# Caution_Panel_control.net
KiCad netlist of a schematic drawn in EAGLE
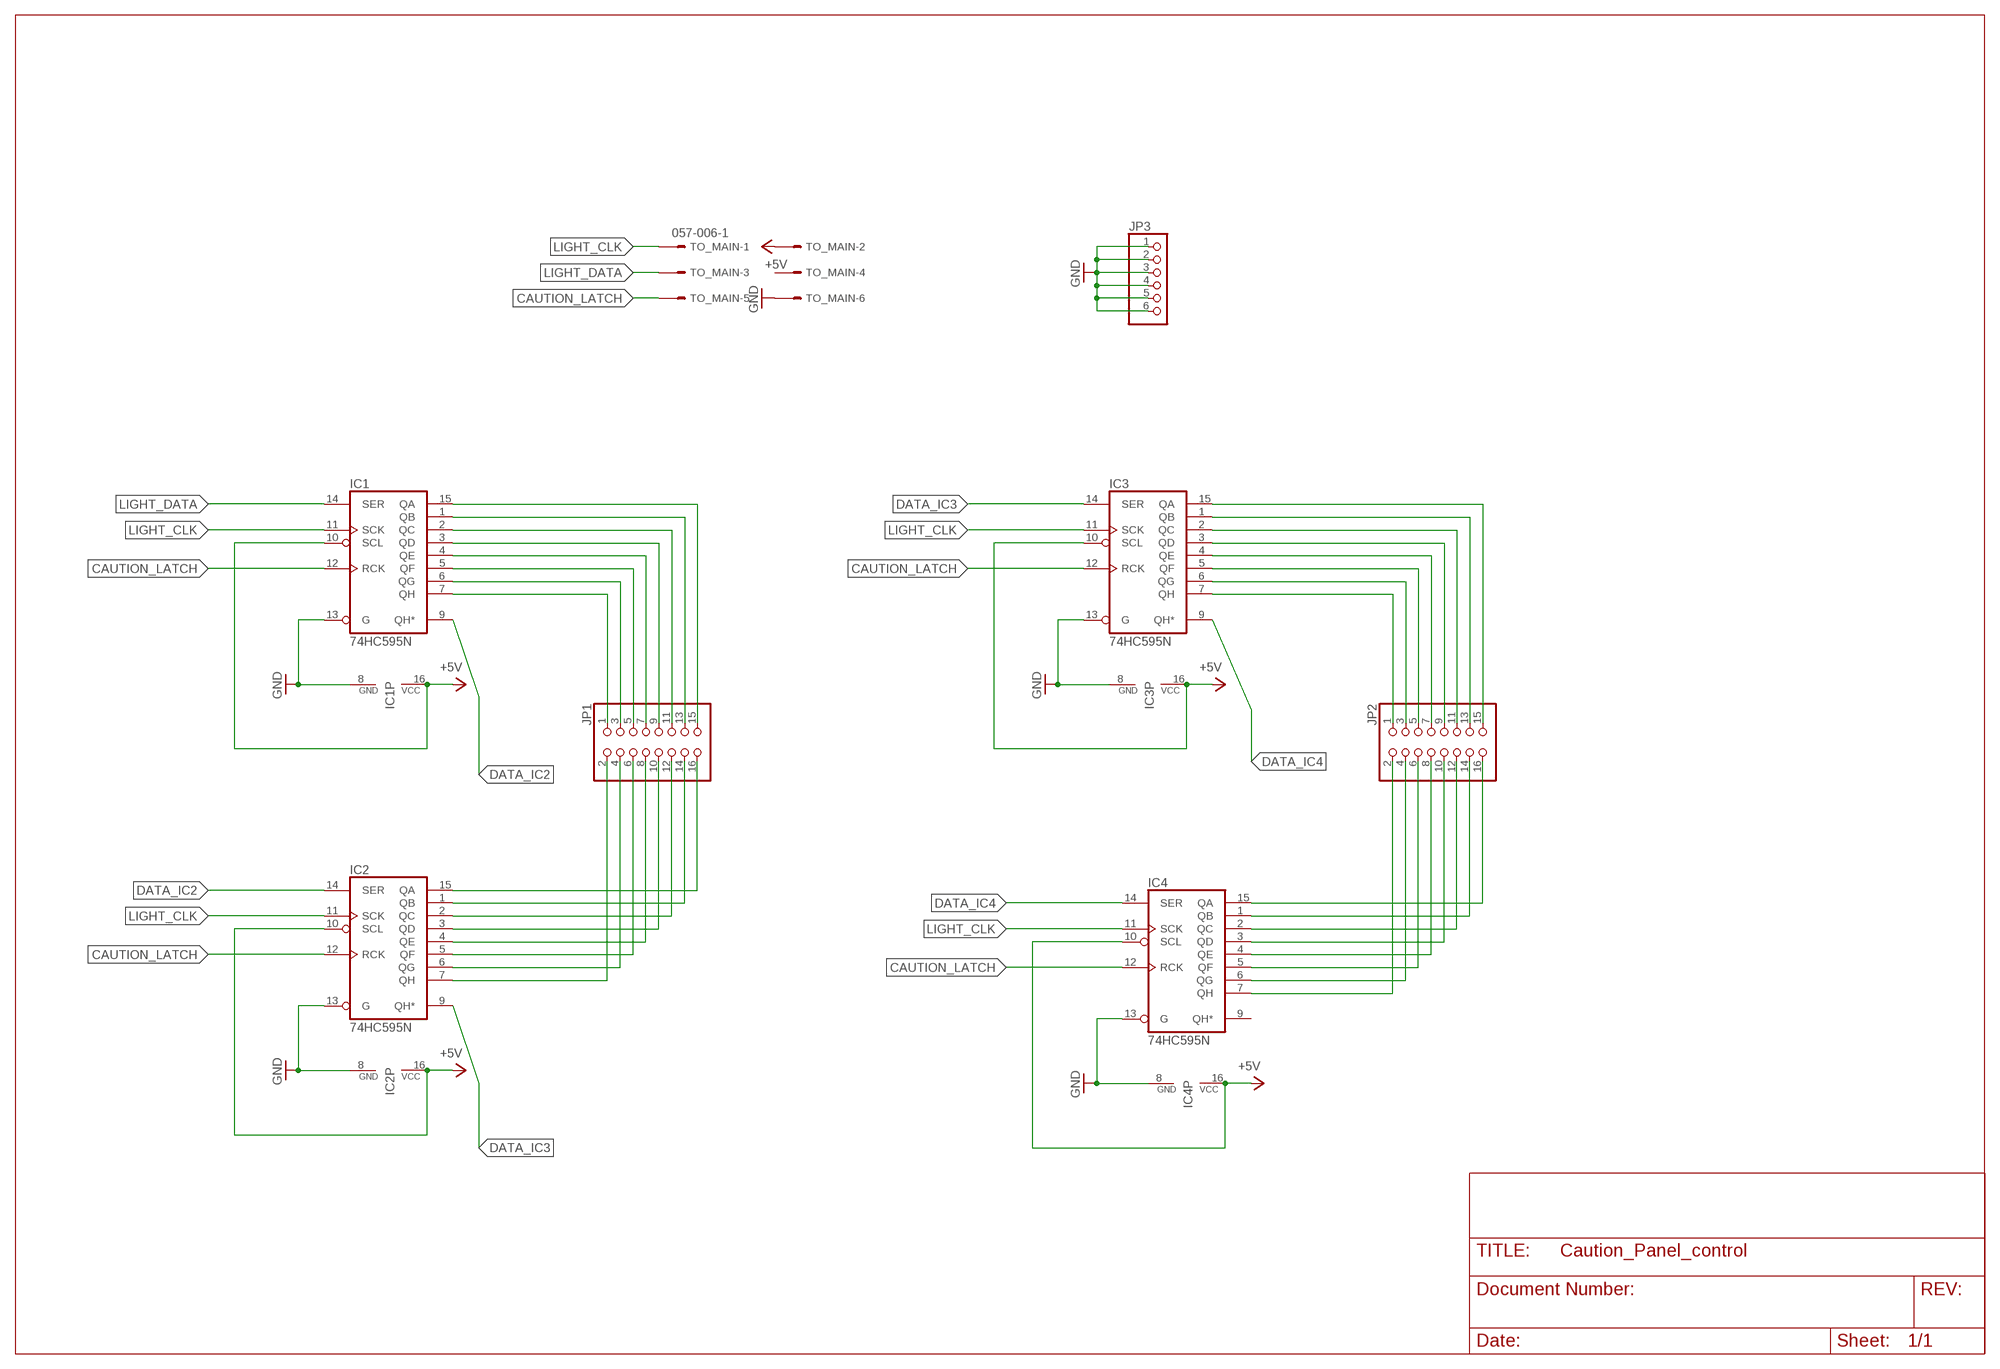
[diagram p0: schematic, sheet 1]

(export (version "E")
  (design (tool "Eeschema 10.0.6"))
  (components
    (comp (ref "IC1")
      (value "74HC595N")
      (footprint "eagle-import:DIL16")
      (libsource (lib "eagle-import") (part "74595NHC"))
    )
    (comp (ref "IC2")
      (value "74HC595N")
      (footprint "eagle-import:DIL16")
      (libsource (lib "eagle-import") (part "74595NHC"))
    )
    (comp (ref "IC3")
      (value "74HC595N")
      (footprint "eagle-import:DIL16")
      (libsource (lib "eagle-import") (part "74595NHC"))
    )
    (comp (ref "IC4")
      (value "74HC595N")
      (footprint "eagle-import:DIL16")
      (libsource (lib "eagle-import") (part "74595NHC"))
    )
    (comp (ref "JP1")
      (value "PINHD-2X8")
      (footprint "eagle-import:2X08")
      (libsource (lib "eagle-import") (part "PINHD-2X8"))
    )
    (comp (ref "JP2")
      (value "PINHD-2X8")
      (footprint "eagle-import:2X08")
      (libsource (lib "eagle-import") (part "PINHD-2X8"))
    )
    (comp (ref "JP3")
      (value "PINHD-1X6")
      (footprint "eagle-import:1X06")
      (libsource (lib "eagle-import") (part "PINHD-1X6"))
    )
    (comp (ref "TO_MAIN")
      (value "057-006-1")
      (footprint "eagle-import:057-006-1")
      (libsource (lib "eagle-import") (part "057-006-1"))
    )
  )
  (nets
    (net (code "1") (name "+5V") (class "Default")
      (node (ref "IC1") (pin "10") (pinfunction "SCL_10") (pintype "input"))
      (node (ref "IC1") (pin "16") (pinfunction "VCC_16") (pintype "power_in"))
      (node (ref "IC2") (pin "10") (pinfunction "SCL_10") (pintype "input"))
      (node (ref "IC2") (pin "16") (pinfunction "VCC_16") (pintype "power_in"))
      (node (ref "IC3") (pin "10") (pinfunction "SCL_10") (pintype "input"))
      (node (ref "IC3") (pin "16") (pinfunction "VCC_16") (pintype "power_in"))
      (node (ref "IC4") (pin "10") (pinfunction "SCL_10") (pintype "input"))
      (node (ref "IC4") (pin "16") (pinfunction "VCC_16") (pintype "power_in"))
      (node (ref "TO_MAIN") (pin "2") (pinfunction "S_2") (pintype "passive"))
    )
    (net (code "2") (name "CAUTION_LATCH") (class "Default")
      (node (ref "IC1") (pin "12") (pinfunction "RCK_12") (pintype "input"))
      (node (ref "IC2") (pin "12") (pinfunction "RCK_12") (pintype "input"))
      (node (ref "IC3") (pin "12") (pinfunction "RCK_12") (pintype "input"))
      (node (ref "IC4") (pin "12") (pinfunction "RCK_12") (pintype "input"))
      (node (ref "TO_MAIN") (pin "5") (pinfunction "S_5") (pintype "passive"))
    )
    (net (code "3") (name "DATA_IC2") (class "Default")
      (node (ref "IC1") (pin "9") (pinfunction "QH*_9") (pintype "tri_state"))
      (node (ref "IC2") (pin "14") (pinfunction "SER_14") (pintype "input"))
    )
    (net (code "4") (name "DATA_IC3") (class "Default")
      (node (ref "IC2") (pin "9") (pinfunction "QH*_9") (pintype "tri_state"))
      (node (ref "IC3") (pin "14") (pinfunction "SER_14") (pintype "input"))
    )
    (net (code "5") (name "DATA_IC4") (class "Default")
      (node (ref "IC3") (pin "9") (pinfunction "QH*_9") (pintype "tri_state"))
      (node (ref "IC4") (pin "14") (pinfunction "SER_14") (pintype "input"))
    )
    (net (code "6") (name "GND") (class "Default")
      (node (ref "IC1") (pin "13") (pinfunction "G_13") (pintype "input"))
      (node (ref "IC1") (pin "8") (pinfunction "GND_8") (pintype "power_in"))
      (node (ref "IC2") (pin "13") (pinfunction "G_13") (pintype "input"))
      (node (ref "IC2") (pin "8") (pinfunction "GND_8") (pintype "power_in"))
      (node (ref "IC3") (pin "13") (pinfunction "G_13") (pintype "input"))
      (node (ref "IC3") (pin "8") (pinfunction "GND_8") (pintype "power_in"))
      (node (ref "IC4") (pin "13") (pinfunction "G_13") (pintype "input"))
      (node (ref "IC4") (pin "8") (pinfunction "GND_8") (pintype "power_in"))
      (node (ref "JP3") (pin "1") (pinfunction "1_1") (pintype "passive"))
      (node (ref "JP3") (pin "2") (pinfunction "2_2") (pintype "passive"))
      (node (ref "JP3") (pin "3") (pinfunction "3_3") (pintype "passive"))
      (node (ref "JP3") (pin "4") (pinfunction "4_4") (pintype "passive"))
      (node (ref "JP3") (pin "5") (pinfunction "5_5") (pintype "passive"))
      (node (ref "JP3") (pin "6") (pinfunction "6_6") (pintype "passive"))
      (node (ref "TO_MAIN") (pin "6") (pinfunction "S_6") (pintype "passive"))
    )
    (net (code "7") (name "LIGHT_CLK") (class "Default")
      (node (ref "IC1") (pin "11") (pinfunction "SCK_11") (pintype "input"))
      (node (ref "IC2") (pin "11") (pinfunction "SCK_11") (pintype "input"))
      (node (ref "IC3") (pin "11") (pinfunction "SCK_11") (pintype "input"))
      (node (ref "IC4") (pin "11") (pinfunction "SCK_11") (pintype "input"))
      (node (ref "TO_MAIN") (pin "1") (pinfunction "S_1") (pintype "passive"))
    )
    (net (code "8") (name "LIGHT_DATA") (class "Default")
      (node (ref "IC1") (pin "14") (pinfunction "SER_14") (pintype "input"))
      (node (ref "TO_MAIN") (pin "3") (pinfunction "S_3") (pintype "passive"))
    )
    (net (code "9") (name "Net-(IC1A-QA)") (class "Default")
      (node (ref "IC1") (pin "15") (pinfunction "QA_15") (pintype "tri_state"))
      (node (ref "JP1") (pin "15") (pinfunction "15_15") (pintype "passive"))
    )
    (net (code "10") (name "Net-(IC1A-QB)") (class "Default")
      (node (ref "IC1") (pin "1") (pinfunction "QB_1") (pintype "tri_state"))
      (node (ref "JP1") (pin "13") (pinfunction "13_13") (pintype "passive"))
    )
    (net (code "11") (name "Net-(IC1A-QC)") (class "Default")
      (node (ref "IC1") (pin "2") (pinfunction "QC_2") (pintype "tri_state"))
      (node (ref "JP1") (pin "11") (pinfunction "11_11") (pintype "passive"))
    )
    (net (code "12") (name "Net-(IC1A-QD)") (class "Default")
      (node (ref "IC1") (pin "3") (pinfunction "QD_3") (pintype "tri_state"))
      (node (ref "JP1") (pin "9") (pinfunction "9_9") (pintype "passive"))
    )
    (net (code "13") (name "Net-(IC1A-QE)") (class "Default")
      (node (ref "IC1") (pin "4") (pinfunction "QE_4") (pintype "tri_state"))
      (node (ref "JP1") (pin "7") (pinfunction "7_7") (pintype "passive"))
    )
    (net (code "14") (name "Net-(IC1A-QF)") (class "Default")
      (node (ref "IC1") (pin "5") (pinfunction "QF_5") (pintype "tri_state"))
      (node (ref "JP1") (pin "5") (pinfunction "5_5") (pintype "passive"))
    )
    (net (code "15") (name "Net-(IC1A-QG)") (class "Default")
      (node (ref "IC1") (pin "6") (pinfunction "QG_6") (pintype "tri_state"))
      (node (ref "JP1") (pin "3") (pinfunction "3_3") (pintype "passive"))
    )
    (net (code "16") (name "Net-(IC1A-QH)") (class "Default")
      (node (ref "IC1") (pin "7") (pinfunction "QH_7") (pintype "tri_state"))
      (node (ref "JP1") (pin "1") (pinfunction "1_1") (pintype "passive"))
    )
    (net (code "17") (name "Net-(IC2A-QA)") (class "Default")
      (node (ref "IC2") (pin "15") (pinfunction "QA_15") (pintype "tri_state"))
      (node (ref "JP1") (pin "16") (pinfunction "16_16") (pintype "passive"))
    )
    (net (code "18") (name "Net-(IC2A-QB)") (class "Default")
      (node (ref "IC2") (pin "1") (pinfunction "QB_1") (pintype "tri_state"))
      (node (ref "JP1") (pin "14") (pinfunction "14_14") (pintype "passive"))
    )
    (net (code "19") (name "Net-(IC2A-QC)") (class "Default")
      (node (ref "IC2") (pin "2") (pinfunction "QC_2") (pintype "tri_state"))
      (node (ref "JP1") (pin "12") (pinfunction "12_12") (pintype "passive"))
    )
    (net (code "20") (name "Net-(IC2A-QD)") (class "Default")
      (node (ref "IC2") (pin "3") (pinfunction "QD_3") (pintype "tri_state"))
      (node (ref "JP1") (pin "10") (pinfunction "10_10") (pintype "passive"))
    )
    (net (code "21") (name "Net-(IC2A-QE)") (class "Default")
      (node (ref "IC2") (pin "4") (pinfunction "QE_4") (pintype "tri_state"))
      (node (ref "JP1") (pin "8") (pinfunction "8_8") (pintype "passive"))
    )
    (net (code "22") (name "Net-(IC2A-QF)") (class "Default")
      (node (ref "IC2") (pin "5") (pinfunction "QF_5") (pintype "tri_state"))
      (node (ref "JP1") (pin "6") (pinfunction "6_6") (pintype "passive"))
    )
    (net (code "23") (name "Net-(IC2A-QG)") (class "Default")
      (node (ref "IC2") (pin "6") (pinfunction "QG_6") (pintype "tri_state"))
      (node (ref "JP1") (pin "4") (pinfunction "4_4") (pintype "passive"))
    )
    (net (code "24") (name "Net-(IC2A-QH)") (class "Default")
      (node (ref "IC2") (pin "7") (pinfunction "QH_7") (pintype "tri_state"))
      (node (ref "JP1") (pin "2") (pinfunction "2_2") (pintype "passive"))
    )
    (net (code "25") (name "Net-(IC3A-QA)") (class "Default")
      (node (ref "IC3") (pin "15") (pinfunction "QA_15") (pintype "tri_state"))
      (node (ref "JP2") (pin "15") (pinfunction "15_15") (pintype "passive"))
    )
    (net (code "26") (name "Net-(IC3A-QB)") (class "Default")
      (node (ref "IC3") (pin "1") (pinfunction "QB_1") (pintype "tri_state"))
      (node (ref "JP2") (pin "13") (pinfunction "13_13") (pintype "passive"))
    )
    (net (code "27") (name "Net-(IC3A-QC)") (class "Default")
      (node (ref "IC3") (pin "2") (pinfunction "QC_2") (pintype "tri_state"))
      (node (ref "JP2") (pin "11") (pinfunction "11_11") (pintype "passive"))
    )
    (net (code "28") (name "Net-(IC3A-QD)") (class "Default")
      (node (ref "IC3") (pin "3") (pinfunction "QD_3") (pintype "tri_state"))
      (node (ref "JP2") (pin "9") (pinfunction "9_9") (pintype "passive"))
    )
    (net (code "29") (name "Net-(IC3A-QE)") (class "Default")
      (node (ref "IC3") (pin "4") (pinfunction "QE_4") (pintype "tri_state"))
      (node (ref "JP2") (pin "7") (pinfunction "7_7") (pintype "passive"))
    )
    (net (code "30") (name "Net-(IC3A-QF)") (class "Default")
      (node (ref "IC3") (pin "5") (pinfunction "QF_5") (pintype "tri_state"))
      (node (ref "JP2") (pin "5") (pinfunction "5_5") (pintype "passive"))
    )
    (net (code "31") (name "Net-(IC3A-QG)") (class "Default")
      (node (ref "IC3") (pin "6") (pinfunction "QG_6") (pintype "tri_state"))
      (node (ref "JP2") (pin "3") (pinfunction "3_3") (pintype "passive"))
    )
    (net (code "32") (name "Net-(IC3A-QH)") (class "Default")
      (node (ref "IC3") (pin "7") (pinfunction "QH_7") (pintype "tri_state"))
      (node (ref "JP2") (pin "1") (pinfunction "1_1") (pintype "passive"))
    )
    (net (code "33") (name "Net-(IC4A-QA)") (class "Default")
      (node (ref "IC4") (pin "15") (pinfunction "QA_15") (pintype "tri_state"))
      (node (ref "JP2") (pin "16") (pinfunction "16_16") (pintype "passive"))
    )
    (net (code "34") (name "Net-(IC4A-QB)") (class "Default")
      (node (ref "IC4") (pin "1") (pinfunction "QB_1") (pintype "tri_state"))
      (node (ref "JP2") (pin "14") (pinfunction "14_14") (pintype "passive"))
    )
    (net (code "35") (name "Net-(IC4A-QC)") (class "Default")
      (node (ref "IC4") (pin "2") (pinfunction "QC_2") (pintype "tri_state"))
      (node (ref "JP2") (pin "12") (pinfunction "12_12") (pintype "passive"))
    )
    (net (code "36") (name "Net-(IC4A-QD)") (class "Default")
      (node (ref "IC4") (pin "3") (pinfunction "QD_3") (pintype "tri_state"))
      (node (ref "JP2") (pin "10") (pinfunction "10_10") (pintype "passive"))
    )
    (net (code "37") (name "Net-(IC4A-QE)") (class "Default")
      (node (ref "IC4") (pin "4") (pinfunction "QE_4") (pintype "tri_state"))
      (node (ref "JP2") (pin "8") (pinfunction "8_8") (pintype "passive"))
    )
    (net (code "38") (name "Net-(IC4A-QF)") (class "Default")
      (node (ref "IC4") (pin "5") (pinfunction "QF_5") (pintype "tri_state"))
      (node (ref "JP2") (pin "6") (pinfunction "6_6") (pintype "passive"))
    )
    (net (code "39") (name "Net-(IC4A-QG)") (class "Default")
      (node (ref "IC4") (pin "6") (pinfunction "QG_6") (pintype "tri_state"))
      (node (ref "JP2") (pin "4") (pinfunction "4_4") (pintype "passive"))
    )
    (net (code "40") (name "Net-(IC4A-QH)") (class "Default")
      (node (ref "IC4") (pin "7") (pinfunction "QH_7") (pintype "tri_state"))
      (node (ref "JP2") (pin "2") (pinfunction "2_2") (pintype "passive"))
    )
    (net (code "41") (name "unconnected-(IC4A-QH*-Pad9)") (class "Default")
      (node (ref "IC4") (pin "9") (pinfunction "QH*_9") (pintype "tri_state"))
    )
    (net (code "42") (name "unconnected-(TO_MAIND-S-Pad4)") (class "Default")
      (node (ref "TO_MAIN") (pin "4") (pinfunction "S_4") (pintype "passive"))
    )
  )
)
